# OutputIndicator_v1p1.net
KiCad netlist of a schematic drawn in EAGLE
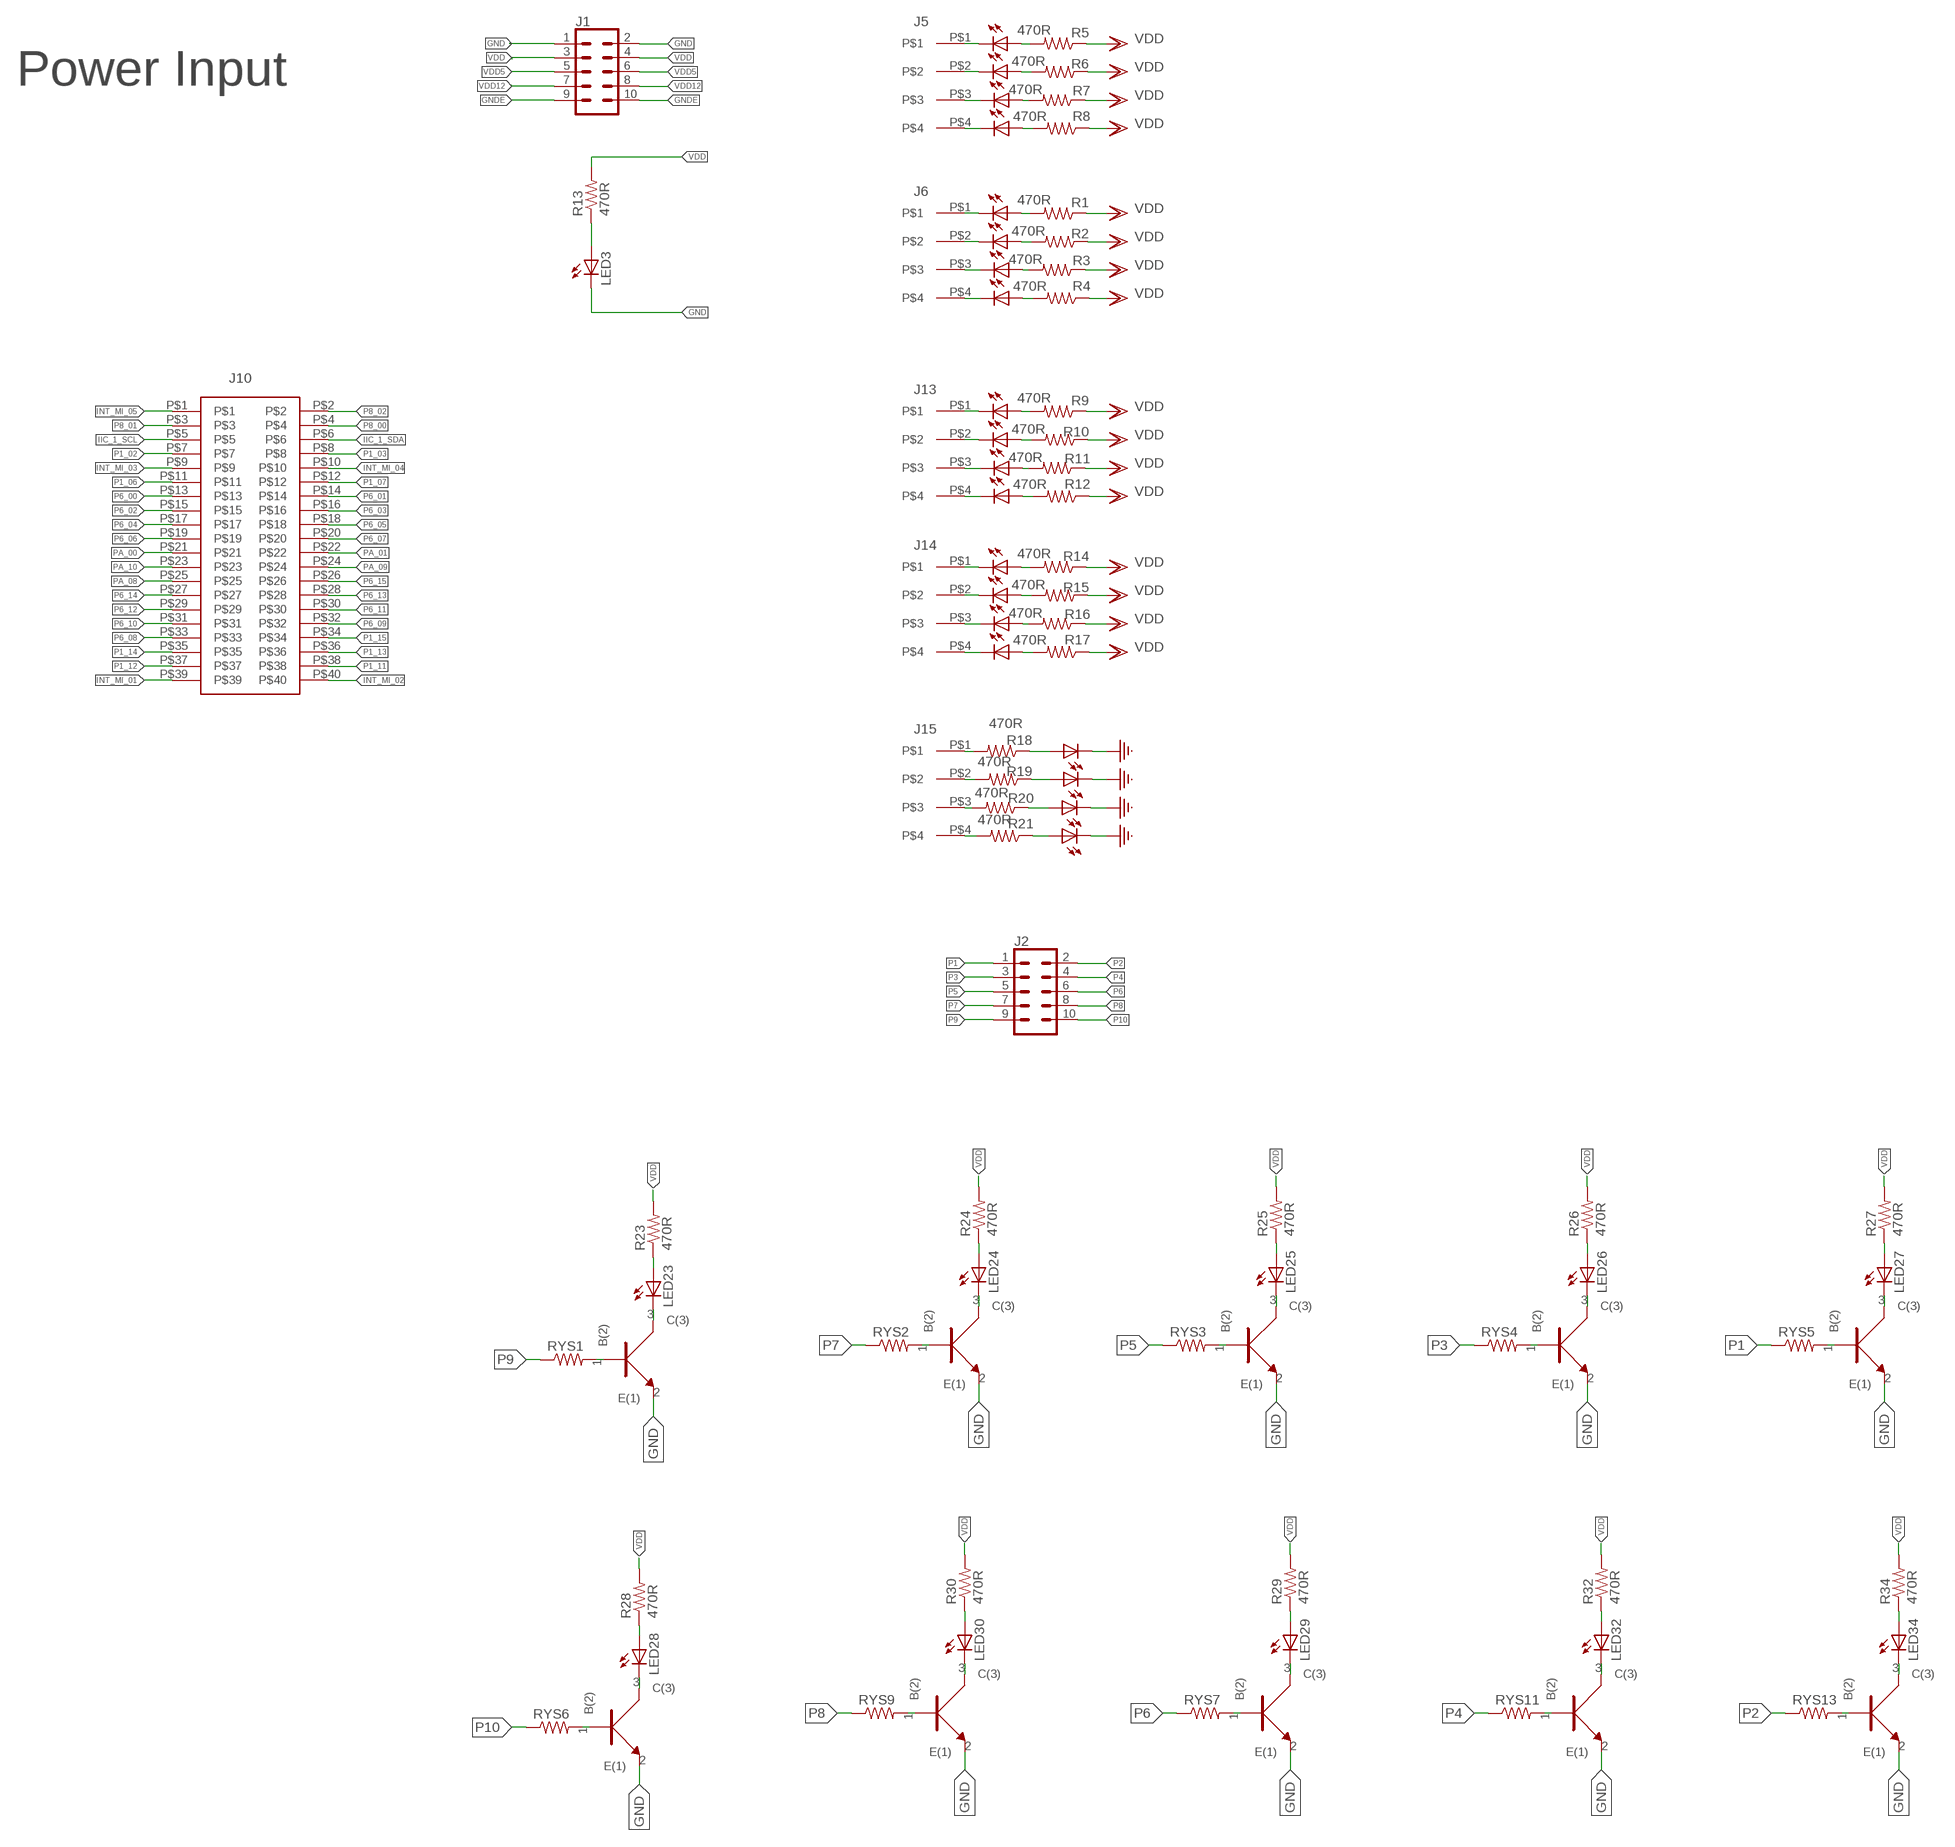
[diagram p0: schematic, sheet 1]

(export (version "E")
  (design (tool "Eeschema 10.0.6"))
  (components
    (comp (ref "J1")
      (value "CONN_05X2PTH")
      (footprint "eagle-import:2X5")
      (libsource (lib "eagle-import") (part "CONN_05X2PTH"))
    )
    (comp (ref "J2")
      (value "CONN_05X2NO_SILK")
      (footprint "eagle-import:2X5_NOSILK")
      (libsource (lib "eagle-import") (part "CONN_05X2NO_SILK"))
    )
    (comp (ref "J5")
      (value "3.81MM_1_X_4_RT_ANGLE_PLUG_HEADER")
      (footprint "eagle-import:1X4_3.81MM_PITCH")
      (libsource (lib "eagle-import") (part "3.81MM_1_X_4_RT_ANGLE_PLUG_HEADER"))
    )
    (comp (ref "J6")
      (value "3.81MM_1_X_4_RT_ANGLE_PLUG_HEADER")
      (footprint "eagle-import:1X4_3.81MM_PITCH")
      (libsource (lib "eagle-import") (part "3.81MM_1_X_4_RT_ANGLE_PLUG_HEADER"))
    )
    (comp (ref "J10")
      (value "HEADER_2_X_20_GENERIC")
      (footprint "eagle-import:HEADER_2_X_20_.1_INCH")
      (libsource (lib "eagle-import") (part "HEADER_2_X_20_GENERIC"))
    )
    (comp (ref "J13")
      (value "3.81MM_1_X_4_RT_ANGLE_PLUG_HEADER")
      (footprint "eagle-import:1X4_3.81MM_PITCH")
      (libsource (lib "eagle-import") (part "3.81MM_1_X_4_RT_ANGLE_PLUG_HEADER"))
    )
    (comp (ref "J14")
      (value "3.81MM_1_X_4_RT_ANGLE_PLUG_HEADER")
      (footprint "eagle-import:1X4_3.81MM_PITCH")
      (libsource (lib "eagle-import") (part "3.81MM_1_X_4_RT_ANGLE_PLUG_HEADER"))
    )
    (comp (ref "J15")
      (value "3.81MM_1_X_4_RT_ANGLE_PLUG_HEADER")
      (footprint "eagle-import:1X4_3.81MM_PITCH")
      (libsource (lib "eagle-import") (part "3.81MM_1_X_4_RT_ANGLE_PLUG_HEADER"))
    )
    (comp (ref "LED1")
      (value "LED_0805_GREEN")
      (footprint "eagle-import:LED_0805_GREEN")
      (libsource (lib "eagle-import") (part "LED_0805_GREEN"))
    )
    (comp (ref "LED2")
      (value "LED_0805_GREEN")
      (footprint "eagle-import:LED_0805_GREEN")
      (libsource (lib "eagle-import") (part "LED_0805_GREEN"))
    )
    (comp (ref "LED3")
      (value "LED_0805_GREEN")
      (footprint "eagle-import:LED_0805_GREEN")
      (libsource (lib "eagle-import") (part "LED_0805_GREEN"))
    )
    (comp (ref "LED4")
      (value "LED_0805_GREEN")
      (footprint "eagle-import:LED_0805_GREEN")
      (libsource (lib "eagle-import") (part "LED_0805_GREEN"))
    )
    (comp (ref "LED5")
      (value "LED_0805_GREEN")
      (footprint "eagle-import:LED_0805_GREEN")
      (libsource (lib "eagle-import") (part "LED_0805_GREEN"))
    )
    (comp (ref "LED6")
      (value "LED_0805_GREEN")
      (footprint "eagle-import:LED_0805_GREEN")
      (libsource (lib "eagle-import") (part "LED_0805_GREEN"))
    )
    (comp (ref "LED7")
      (value "LED_0805_GREEN")
      (footprint "eagle-import:LED_0805_GREEN")
      (libsource (lib "eagle-import") (part "LED_0805_GREEN"))
    )
    (comp (ref "LED8")
      (value "LED_0805_GREEN")
      (footprint "eagle-import:LED_0805_GREEN")
      (libsource (lib "eagle-import") (part "LED_0805_GREEN"))
    )
    (comp (ref "LED9")
      (value "LED_0805_GREEN")
      (footprint "eagle-import:LED_0805_GREEN")
      (libsource (lib "eagle-import") (part "LED_0805_GREEN"))
    )
    (comp (ref "LED10")
      (value "LED_0805_GREEN")
      (footprint "eagle-import:LED_0805_GREEN")
      (libsource (lib "eagle-import") (part "LED_0805_GREEN"))
    )
    (comp (ref "LED11")
      (value "LED_0805_GREEN")
      (footprint "eagle-import:LED_0805_GREEN")
      (libsource (lib "eagle-import") (part "LED_0805_GREEN"))
    )
    (comp (ref "LED12")
      (value "LED_0805_GREEN")
      (footprint "eagle-import:LED_0805_GREEN")
      (libsource (lib "eagle-import") (part "LED_0805_GREEN"))
    )
    (comp (ref "LED13")
      (value "LED_0805_GREEN")
      (footprint "eagle-import:LED_0805_GREEN")
      (libsource (lib "eagle-import") (part "LED_0805_GREEN"))
    )
    (comp (ref "LED14")
      (value "LED_0805_GREEN")
      (footprint "eagle-import:LED_0805_GREEN")
      (libsource (lib "eagle-import") (part "LED_0805_GREEN"))
    )
    (comp (ref "LED15")
      (value "LED_0805_GREEN")
      (footprint "eagle-import:LED_0805_GREEN")
      (libsource (lib "eagle-import") (part "LED_0805_GREEN"))
    )
    (comp (ref "LED16")
      (value "LED_0805_GREEN")
      (footprint "eagle-import:LED_0805_GREEN")
      (libsource (lib "eagle-import") (part "LED_0805_GREEN"))
    )
    (comp (ref "LED17")
      (value "LED_0805_GREEN")
      (footprint "eagle-import:LED_0805_GREEN")
      (libsource (lib "eagle-import") (part "LED_0805_GREEN"))
    )
    (comp (ref "LED18")
      (value "LED_0805_GREEN")
      (footprint "eagle-import:LED_0805_GREEN")
      (libsource (lib "eagle-import") (part "LED_0805_GREEN"))
    )
    (comp (ref "LED19")
      (value "LED_0805_GREEN")
      (footprint "eagle-import:LED_0805_GREEN")
      (libsource (lib "eagle-import") (part "LED_0805_GREEN"))
    )
    (comp (ref "LED20")
      (value "LED_0805_GREEN")
      (footprint "eagle-import:LED_0805_GREEN")
      (libsource (lib "eagle-import") (part "LED_0805_GREEN"))
    )
    (comp (ref "LED21")
      (value "LED_0805_GREEN")
      (footprint "eagle-import:LED_0805_GREEN")
      (libsource (lib "eagle-import") (part "LED_0805_GREEN"))
    )
    (comp (ref "LED23")
      (value "LED_0805_GREEN")
      (footprint "eagle-import:LED_0805_GREEN")
      (libsource (lib "eagle-import") (part "LED_0805_GREEN"))
    )
    (comp (ref "LED24")
      (value "LED_0805_GREEN")
      (footprint "eagle-import:LED_0805_GREEN")
      (libsource (lib "eagle-import") (part "LED_0805_GREEN"))
    )
    (comp (ref "LED25")
      (value "LED_0805_GREEN")
      (footprint "eagle-import:LED_0805_GREEN")
      (libsource (lib "eagle-import") (part "LED_0805_GREEN"))
    )
    (comp (ref "LED26")
      (value "LED_0805_GREEN")
      (footprint "eagle-import:LED_0805_GREEN")
      (libsource (lib "eagle-import") (part "LED_0805_GREEN"))
    )
    (comp (ref "LED27")
      (value "LED_0805_GREEN")
      (footprint "eagle-import:LED_0805_GREEN")
      (libsource (lib "eagle-import") (part "LED_0805_GREEN"))
    )
    (comp (ref "LED28")
      (value "LED_0805_GREEN")
      (footprint "eagle-import:LED_0805_GREEN")
      (libsource (lib "eagle-import") (part "LED_0805_GREEN"))
    )
    (comp (ref "LED29")
      (value "LED_0805_GREEN")
      (footprint "eagle-import:LED_0805_GREEN")
      (libsource (lib "eagle-import") (part "LED_0805_GREEN"))
    )
    (comp (ref "LED30")
      (value "LED_0805_GREEN")
      (footprint "eagle-import:LED_0805_GREEN")
      (libsource (lib "eagle-import") (part "LED_0805_GREEN"))
    )
    (comp (ref "LED32")
      (value "LED_0805_GREEN")
      (footprint "eagle-import:LED_0805_GREEN")
      (libsource (lib "eagle-import") (part "LED_0805_GREEN"))
    )
    (comp (ref "LED34")
      (value "LED_0805_GREEN")
      (footprint "eagle-import:LED_0805_GREEN")
      (libsource (lib "eagle-import") (part "LED_0805_GREEN"))
    )
    (comp (ref "R1")
      (value "470R")
      (footprint "eagle-import:0402")
      (libsource (lib "eagle-import") (part "R_0402"))
    )
    (comp (ref "R2")
      (value "470R")
      (footprint "eagle-import:0402")
      (libsource (lib "eagle-import") (part "R_0402"))
    )
    (comp (ref "R3")
      (value "470R")
      (footprint "eagle-import:0402")
      (libsource (lib "eagle-import") (part "R_0402"))
    )
    (comp (ref "R4")
      (value "470R")
      (footprint "eagle-import:0402")
      (libsource (lib "eagle-import") (part "R_0402"))
    )
    (comp (ref "R5")
      (value "470R")
      (footprint "eagle-import:0402")
      (libsource (lib "eagle-import") (part "R_0402"))
    )
    (comp (ref "R6")
      (value "470R")
      (footprint "eagle-import:0402")
      (libsource (lib "eagle-import") (part "R_0402"))
    )
    (comp (ref "R7")
      (value "470R")
      (footprint "eagle-import:0402")
      (libsource (lib "eagle-import") (part "R_0402"))
    )
    (comp (ref "R8")
      (value "470R")
      (footprint "eagle-import:0402")
      (libsource (lib "eagle-import") (part "R_0402"))
    )
    (comp (ref "R9")
      (value "470R")
      (footprint "eagle-import:0402")
      (libsource (lib "eagle-import") (part "R_0402"))
    )
    (comp (ref "R10")
      (value "470R")
      (footprint "eagle-import:0402")
      (libsource (lib "eagle-import") (part "R_0402"))
    )
    (comp (ref "R11")
      (value "470R")
      (footprint "eagle-import:0402")
      (libsource (lib "eagle-import") (part "R_0402"))
    )
    (comp (ref "R12")
      (value "470R")
      (footprint "eagle-import:0402")
      (libsource (lib "eagle-import") (part "R_0402"))
    )
    (comp (ref "R13")
      (value "470R")
      (footprint "eagle-import:0402")
      (libsource (lib "eagle-import") (part "R_0402"))
    )
    (comp (ref "R14")
      (value "470R")
      (footprint "eagle-import:0402")
      (libsource (lib "eagle-import") (part "R_0402"))
    )
    (comp (ref "R15")
      (value "470R")
      (footprint "eagle-import:0402")
      (libsource (lib "eagle-import") (part "R_0402"))
    )
    (comp (ref "R16")
      (value "470R")
      (footprint "eagle-import:0402")
      (libsource (lib "eagle-import") (part "R_0402"))
    )
    (comp (ref "R17")
      (value "470R")
      (footprint "eagle-import:0402")
      (libsource (lib "eagle-import") (part "R_0402"))
    )
    (comp (ref "R18")
      (value "470R")
      (footprint "eagle-import:0402")
      (libsource (lib "eagle-import") (part "R_0402"))
    )
    (comp (ref "R19")
      (value "470R")
      (footprint "eagle-import:0402")
      (libsource (lib "eagle-import") (part "R_0402"))
    )
    (comp (ref "R20")
      (value "470R")
      (footprint "eagle-import:0402")
      (libsource (lib "eagle-import") (part "R_0402"))
    )
    (comp (ref "R21")
      (value "470R")
      (footprint "eagle-import:0402")
      (libsource (lib "eagle-import") (part "R_0402"))
    )
    (comp (ref "R23")
      (value "470R")
      (footprint "eagle-import:0402")
      (libsource (lib "eagle-import") (part "R_0402"))
    )
    (comp (ref "R24")
      (value "470R")
      (footprint "eagle-import:0402")
      (libsource (lib "eagle-import") (part "R_0402"))
    )
    (comp (ref "R25")
      (value "470R")
      (footprint "eagle-import:0402")
      (libsource (lib "eagle-import") (part "R_0402"))
    )
    (comp (ref "R26")
      (value "470R")
      (footprint "eagle-import:0402")
      (libsource (lib "eagle-import") (part "R_0402"))
    )
    (comp (ref "R27")
      (value "470R")
      (footprint "eagle-import:0402")
      (libsource (lib "eagle-import") (part "R_0402"))
    )
    (comp (ref "R28")
      (value "470R")
      (footprint "eagle-import:0402")
      (libsource (lib "eagle-import") (part "R_0402"))
    )
    (comp (ref "R29")
      (value "470R")
      (footprint "eagle-import:0402")
      (libsource (lib "eagle-import") (part "R_0402"))
    )
    (comp (ref "R30")
      (value "470R")
      (footprint "eagle-import:0402")
      (libsource (lib "eagle-import") (part "R_0402"))
    )
    (comp (ref "R32")
      (value "470R")
      (footprint "eagle-import:0402")
      (libsource (lib "eagle-import") (part "R_0402"))
    )
    (comp (ref "R34")
      (value "470R")
      (footprint "eagle-import:0402")
      (libsource (lib "eagle-import") (part "R_0402"))
    )
    (comp (ref "RYS1")
      (value "1K")
      (footprint "eagle-import:0402")
      (libsource (lib "eagle-import") (part "R_0402"))
    )
    (comp (ref "RYS2")
      (value "1K")
      (footprint "eagle-import:0402")
      (libsource (lib "eagle-import") (part "R_0402"))
    )
    (comp (ref "RYS3")
      (value "1K")
      (footprint "eagle-import:0402")
      (libsource (lib "eagle-import") (part "R_0402"))
    )
    (comp (ref "RYS4")
      (value "1K")
      (footprint "eagle-import:0402")
      (libsource (lib "eagle-import") (part "R_0402"))
    )
    (comp (ref "RYS5")
      (value "1K")
      (footprint "eagle-import:0402")
      (libsource (lib "eagle-import") (part "R_0402"))
    )
    (comp (ref "RYS6")
      (value "1K")
      (footprint "eagle-import:0402")
      (libsource (lib "eagle-import") (part "R_0402"))
    )
    (comp (ref "RYS7")
      (value "1K")
      (footprint "eagle-import:0402")
      (libsource (lib "eagle-import") (part "R_0402"))
    )
    (comp (ref "RYS9")
      (value "1K")
      (footprint "eagle-import:0402")
      (libsource (lib "eagle-import") (part "R_0402"))
    )
    (comp (ref "RYS11")
      (value "1K")
      (footprint "eagle-import:0402")
      (libsource (lib "eagle-import") (part "R_0402"))
    )
    (comp (ref "RYS13")
      (value "1K")
      (footprint "eagle-import:0402")
      (libsource (lib "eagle-import") (part "R_0402"))
    )
    (comp (ref "U1")
      (value "BC846BW")
      (footprint "eagle-import:SOT323")
      (libsource (lib "eagle-import") (part "BC846BW"))
    )
    (comp (ref "U2")
      (value "BC846BW")
      (footprint "eagle-import:SOT323")
      (libsource (lib "eagle-import") (part "BC846BW"))
    )
    (comp (ref "U3")
      (value "BC846BW")
      (footprint "eagle-import:SOT323")
      (libsource (lib "eagle-import") (part "BC846BW"))
    )
    (comp (ref "U4")
      (value "BC846BW")
      (footprint "eagle-import:SOT323")
      (libsource (lib "eagle-import") (part "BC846BW"))
    )
    (comp (ref "U5")
      (value "BC846BW")
      (footprint "eagle-import:SOT323")
      (libsource (lib "eagle-import") (part "BC846BW"))
    )
    (comp (ref "U6")
      (value "BC846BW")
      (footprint "eagle-import:SOT323")
      (libsource (lib "eagle-import") (part "BC846BW"))
    )
    (comp (ref "U7")
      (value "BC846BW")
      (footprint "eagle-import:SOT323")
      (libsource (lib "eagle-import") (part "BC846BW"))
    )
    (comp (ref "U8")
      (value "BC846BW")
      (footprint "eagle-import:SOT323")
      (libsource (lib "eagle-import") (part "BC846BW"))
    )
    (comp (ref "U10")
      (value "BC846BW")
      (footprint "eagle-import:SOT323")
      (libsource (lib "eagle-import") (part "BC846BW"))
    )
    (comp (ref "U12")
      (value "BC846BW")
      (footprint "eagle-import:SOT323")
      (libsource (lib "eagle-import") (part "BC846BW"))
    )
  )
  (nets
    (net (code "1") (name "GND") (class "Default")
      (node (ref "J1") (pin "1") (pinfunction "1_1") (pintype "passive"))
      (node (ref "J1") (pin "2") (pinfunction "2_2") (pintype "passive"))
      (node (ref "LED18") (pin "C") (pinfunction "C_C") (pintype "passive"))
      (node (ref "LED19") (pin "C") (pinfunction "C_C") (pintype "passive"))
      (node (ref "LED20") (pin "C") (pinfunction "C_C") (pintype "passive"))
      (node (ref "LED21") (pin "C") (pinfunction "C_C") (pintype "passive"))
      (node (ref "LED3") (pin "C") (pinfunction "C_C") (pintype "passive"))
      (node (ref "U1") (pin "2") (pinfunction "E(1)_2") (pintype "output"))
      (node (ref "U10") (pin "2") (pinfunction "E(1)_2") (pintype "output"))
      (node (ref "U12") (pin "2") (pinfunction "E(1)_2") (pintype "output"))
      (node (ref "U2") (pin "2") (pinfunction "E(1)_2") (pintype "output"))
      (node (ref "U3") (pin "2") (pinfunction "E(1)_2") (pintype "output"))
      (node (ref "U4") (pin "2") (pinfunction "E(1)_2") (pintype "output"))
      (node (ref "U5") (pin "2") (pinfunction "E(1)_2") (pintype "output"))
      (node (ref "U6") (pin "2") (pinfunction "E(1)_2") (pintype "output"))
      (node (ref "U7") (pin "2") (pinfunction "E(1)_2") (pintype "output"))
      (node (ref "U8") (pin "2") (pinfunction "E(1)_2") (pintype "output"))
    )
    (net (code "2") (name "GNDE") (class "Default")
      (node (ref "J1") (pin "10") (pinfunction "10_10") (pintype "passive"))
      (node (ref "J1") (pin "9") (pinfunction "9_9") (pintype "passive"))
    )
    (net (code "3") (name "IIC_1_SCL") (class "Default")
      (node (ref "J10") (pin "P$5") (pinfunction "P$5_P$5") (pintype "bidirectional"))
    )
    (net (code "4") (name "IIC_1_SDA") (class "Default")
      (node (ref "J10") (pin "P$6") (pinfunction "P$6_P$6") (pintype "bidirectional"))
    )
    (net (code "5") (name "INT_MI_01") (class "Default")
      (node (ref "J10") (pin "P$39") (pinfunction "P$39_P$39") (pintype "bidirectional"))
    )
    (net (code "6") (name "INT_MI_02") (class "Default")
      (node (ref "J10") (pin "P$40") (pinfunction "P$40_P$40") (pintype "bidirectional"))
    )
    (net (code "7") (name "INT_MI_03") (class "Default")
      (node (ref "J10") (pin "P$9") (pinfunction "P$9_P$9") (pintype "bidirectional"))
    )
    (net (code "8") (name "INT_MI_04") (class "Default")
      (node (ref "J10") (pin "P$10") (pinfunction "P$10_P$10") (pintype "bidirectional"))
    )
    (net (code "9") (name "INT_MI_05") (class "Default")
      (node (ref "J10") (pin "P$1") (pinfunction "P$1_P$1") (pintype "bidirectional"))
    )
    (net (code "10") (name "Net-(J5-PadP$1)") (class "Default")
      (node (ref "J5") (pin "P$1") (pinfunction "P$1_P$1") (pintype "bidirectional"))
      (node (ref "LED6") (pin "C") (pinfunction "C_C") (pintype "passive"))
    )
    (net (code "11") (name "Net-(J5-PadP$2)") (class "Default")
      (node (ref "J5") (pin "P$2") (pinfunction "P$2_P$2") (pintype "bidirectional"))
      (node (ref "LED7") (pin "C") (pinfunction "C_C") (pintype "passive"))
    )
    (net (code "12") (name "Net-(J5-PadP$3)") (class "Default")
      (node (ref "J5") (pin "P$3") (pinfunction "P$3_P$3") (pintype "bidirectional"))
      (node (ref "LED8") (pin "C") (pinfunction "C_C") (pintype "passive"))
    )
    (net (code "13") (name "Net-(J5-PadP$4)") (class "Default")
      (node (ref "J5") (pin "P$4") (pinfunction "P$4_P$4") (pintype "bidirectional"))
      (node (ref "LED9") (pin "C") (pinfunction "C_C") (pintype "passive"))
    )
    (net (code "14") (name "Net-(J6-PadP$1)") (class "Default")
      (node (ref "J6") (pin "P$1") (pinfunction "P$1_P$1") (pintype "bidirectional"))
      (node (ref "LED1") (pin "C") (pinfunction "C_C") (pintype "passive"))
    )
    (net (code "15") (name "Net-(J6-PadP$2)") (class "Default")
      (node (ref "J6") (pin "P$2") (pinfunction "P$2_P$2") (pintype "bidirectional"))
      (node (ref "LED2") (pin "C") (pinfunction "C_C") (pintype "passive"))
    )
    (net (code "16") (name "Net-(J6-PadP$3)") (class "Default")
      (node (ref "J6") (pin "P$3") (pinfunction "P$3_P$3") (pintype "bidirectional"))
      (node (ref "LED4") (pin "C") (pinfunction "C_C") (pintype "passive"))
    )
    (net (code "17") (name "Net-(J6-PadP$4)") (class "Default")
      (node (ref "J6") (pin "P$4") (pinfunction "P$4_P$4") (pintype "bidirectional"))
      (node (ref "LED5") (pin "C") (pinfunction "C_C") (pintype "passive"))
    )
    (net (code "18") (name "Net-(J13-PadP$1)") (class "Default")
      (node (ref "J13") (pin "P$1") (pinfunction "P$1_P$1") (pintype "bidirectional"))
      (node (ref "LED10") (pin "C") (pinfunction "C_C") (pintype "passive"))
    )
    (net (code "19") (name "Net-(J13-PadP$2)") (class "Default")
      (node (ref "J13") (pin "P$2") (pinfunction "P$2_P$2") (pintype "bidirectional"))
      (node (ref "LED11") (pin "C") (pinfunction "C_C") (pintype "passive"))
    )
    (net (code "20") (name "Net-(J13-PadP$3)") (class "Default")
      (node (ref "J13") (pin "P$3") (pinfunction "P$3_P$3") (pintype "bidirectional"))
      (node (ref "LED12") (pin "C") (pinfunction "C_C") (pintype "passive"))
    )
    (net (code "21") (name "Net-(J13-PadP$4)") (class "Default")
      (node (ref "J13") (pin "P$4") (pinfunction "P$4_P$4") (pintype "bidirectional"))
      (node (ref "LED13") (pin "C") (pinfunction "C_C") (pintype "passive"))
    )
    (net (code "22") (name "Net-(J14-PadP$1)") (class "Default")
      (node (ref "J14") (pin "P$1") (pinfunction "P$1_P$1") (pintype "bidirectional"))
      (node (ref "LED14") (pin "C") (pinfunction "C_C") (pintype "passive"))
    )
    (net (code "23") (name "Net-(J14-PadP$2)") (class "Default")
      (node (ref "J14") (pin "P$2") (pinfunction "P$2_P$2") (pintype "bidirectional"))
      (node (ref "LED15") (pin "C") (pinfunction "C_C") (pintype "passive"))
    )
    (net (code "24") (name "Net-(J14-PadP$3)") (class "Default")
      (node (ref "J14") (pin "P$3") (pinfunction "P$3_P$3") (pintype "bidirectional"))
      (node (ref "LED16") (pin "C") (pinfunction "C_C") (pintype "passive"))
    )
    (net (code "25") (name "Net-(J14-PadP$4)") (class "Default")
      (node (ref "J14") (pin "P$4") (pinfunction "P$4_P$4") (pintype "bidirectional"))
      (node (ref "LED17") (pin "C") (pinfunction "C_C") (pintype "passive"))
    )
    (net (code "26") (name "Net-(R1-2)") (class "Default")
      (node (ref "LED1") (pin "A") (pinfunction "A_A") (pintype "passive"))
      (node (ref "R1") (pin "P$2") (pinfunction "2_P$2") (pintype "passive"))
    )
    (net (code "27") (name "Net-(R2-2)") (class "Default")
      (node (ref "LED2") (pin "A") (pinfunction "A_A") (pintype "passive"))
      (node (ref "R2") (pin "P$2") (pinfunction "2_P$2") (pintype "passive"))
    )
    (net (code "28") (name "Net-(R3-2)") (class "Default")
      (node (ref "LED4") (pin "A") (pinfunction "A_A") (pintype "passive"))
      (node (ref "R3") (pin "P$2") (pinfunction "2_P$2") (pintype "passive"))
    )
    (net (code "29") (name "Net-(R4-2)") (class "Default")
      (node (ref "LED5") (pin "A") (pinfunction "A_A") (pintype "passive"))
      (node (ref "R4") (pin "P$2") (pinfunction "2_P$2") (pintype "passive"))
    )
    (net (code "30") (name "Net-(R5-2)") (class "Default")
      (node (ref "LED6") (pin "A") (pinfunction "A_A") (pintype "passive"))
      (node (ref "R5") (pin "P$2") (pinfunction "2_P$2") (pintype "passive"))
    )
    (net (code "31") (name "Net-(R6-2)") (class "Default")
      (node (ref "LED7") (pin "A") (pinfunction "A_A") (pintype "passive"))
      (node (ref "R6") (pin "P$2") (pinfunction "2_P$2") (pintype "passive"))
    )
    (net (code "32") (name "Net-(R7-2)") (class "Default")
      (node (ref "LED8") (pin "A") (pinfunction "A_A") (pintype "passive"))
      (node (ref "R7") (pin "P$2") (pinfunction "2_P$2") (pintype "passive"))
    )
    (net (code "33") (name "Net-(R8-2)") (class "Default")
      (node (ref "LED9") (pin "A") (pinfunction "A_A") (pintype "passive"))
      (node (ref "R8") (pin "P$2") (pinfunction "2_P$2") (pintype "passive"))
    )
    (net (code "34") (name "Net-(R9-2)") (class "Default")
      (node (ref "LED10") (pin "A") (pinfunction "A_A") (pintype "passive"))
      (node (ref "R9") (pin "P$2") (pinfunction "2_P$2") (pintype "passive"))
    )
    (net (code "35") (name "Net-(R10-2)") (class "Default")
      (node (ref "LED11") (pin "A") (pinfunction "A_A") (pintype "passive"))
      (node (ref "R10") (pin "P$2") (pinfunction "2_P$2") (pintype "passive"))
    )
    (net (code "36") (name "Net-(R11-2)") (class "Default")
      (node (ref "LED12") (pin "A") (pinfunction "A_A") (pintype "passive"))
      (node (ref "R11") (pin "P$2") (pinfunction "2_P$2") (pintype "passive"))
    )
    (net (code "37") (name "Net-(R12-2)") (class "Default")
      (node (ref "LED13") (pin "A") (pinfunction "A_A") (pintype "passive"))
      (node (ref "R12") (pin "P$2") (pinfunction "2_P$2") (pintype "passive"))
    )
    (net (code "38") (name "Net-(R13-1)") (class "Default")
      (node (ref "LED3") (pin "A") (pinfunction "A_A") (pintype "passive"))
      (node (ref "R13") (pin "P$1") (pinfunction "1_P$1") (pintype "passive"))
    )
    (net (code "39") (name "Net-(R14-2)") (class "Default")
      (node (ref "LED14") (pin "A") (pinfunction "A_A") (pintype "passive"))
      (node (ref "R14") (pin "P$2") (pinfunction "2_P$2") (pintype "passive"))
    )
    (net (code "40") (name "Net-(R15-2)") (class "Default")
      (node (ref "LED15") (pin "A") (pinfunction "A_A") (pintype "passive"))
      (node (ref "R15") (pin "P$2") (pinfunction "2_P$2") (pintype "passive"))
    )
    (net (code "41") (name "Net-(R16-2)") (class "Default")
      (node (ref "LED16") (pin "A") (pinfunction "A_A") (pintype "passive"))
      (node (ref "R16") (pin "P$2") (pinfunction "2_P$2") (pintype "passive"))
    )
    (net (code "42") (name "Net-(R17-2)") (class "Default")
      (node (ref "LED17") (pin "A") (pinfunction "A_A") (pintype "passive"))
      (node (ref "R17") (pin "P$2") (pinfunction "2_P$2") (pintype "passive"))
    )
    (net (code "43") (name "Net-(R18-1)") (class "Default")
      (node (ref "LED18") (pin "A") (pinfunction "A_A") (pintype "passive"))
      (node (ref "R18") (pin "P$1") (pinfunction "1_P$1") (pintype "passive"))
    )
    (net (code "44") (name "Net-(R18-2)") (class "Default")
      (node (ref "J15") (pin "P$1") (pinfunction "P$1_P$1") (pintype "bidirectional"))
      (node (ref "R18") (pin "P$2") (pinfunction "2_P$2") (pintype "passive"))
    )
    (net (code "45") (name "Net-(R19-1)") (class "Default")
      (node (ref "LED19") (pin "A") (pinfunction "A_A") (pintype "passive"))
      (node (ref "R19") (pin "P$1") (pinfunction "1_P$1") (pintype "passive"))
    )
    (net (code "46") (name "Net-(R19-2)") (class "Default")
      (node (ref "J15") (pin "P$2") (pinfunction "P$2_P$2") (pintype "bidirectional"))
      (node (ref "R19") (pin "P$2") (pinfunction "2_P$2") (pintype "passive"))
    )
    (net (code "47") (name "Net-(R20-1)") (class "Default")
      (node (ref "LED20") (pin "A") (pinfunction "A_A") (pintype "passive"))
      (node (ref "R20") (pin "P$1") (pinfunction "1_P$1") (pintype "passive"))
    )
    (net (code "48") (name "Net-(R20-2)") (class "Default")
      (node (ref "J15") (pin "P$3") (pinfunction "P$3_P$3") (pintype "bidirectional"))
      (node (ref "R20") (pin "P$2") (pinfunction "2_P$2") (pintype "passive"))
    )
    (net (code "49") (name "Net-(R21-1)") (class "Default")
      (node (ref "LED21") (pin "A") (pinfunction "A_A") (pintype "passive"))
      (node (ref "R21") (pin "P$1") (pinfunction "1_P$1") (pintype "passive"))
    )
    (net (code "50") (name "Net-(R21-2)") (class "Default")
      (node (ref "J15") (pin "P$4") (pinfunction "P$4_P$4") (pintype "bidirectional"))
      (node (ref "R21") (pin "P$2") (pinfunction "2_P$2") (pintype "passive"))
    )
    (net (code "51") (name "Net-(R23-1)") (class "Default")
      (node (ref "LED23") (pin "A") (pinfunction "A_A") (pintype "passive"))
      (node (ref "R23") (pin "P$1") (pinfunction "1_P$1") (pintype "passive"))
    )
    (net (code "52") (name "Net-(R24-1)") (class "Default")
      (node (ref "LED24") (pin "A") (pinfunction "A_A") (pintype "passive"))
      (node (ref "R24") (pin "P$1") (pinfunction "1_P$1") (pintype "passive"))
    )
    (net (code "53") (name "Net-(R25-1)") (class "Default")
      (node (ref "LED25") (pin "A") (pinfunction "A_A") (pintype "passive"))
      (node (ref "R25") (pin "P$1") (pinfunction "1_P$1") (pintype "passive"))
    )
    (net (code "54") (name "Net-(R26-1)") (class "Default")
      (node (ref "LED26") (pin "A") (pinfunction "A_A") (pintype "passive"))
      (node (ref "R26") (pin "P$1") (pinfunction "1_P$1") (pintype "passive"))
    )
    (net (code "55") (name "Net-(R27-1)") (class "Default")
      (node (ref "LED27") (pin "A") (pinfunction "A_A") (pintype "passive"))
      (node (ref "R27") (pin "P$1") (pinfunction "1_P$1") (pintype "passive"))
    )
    (net (code "56") (name "Net-(R28-1)") (class "Default")
      (node (ref "LED28") (pin "A") (pinfunction "A_A") (pintype "passive"))
      (node (ref "R28") (pin "P$1") (pinfunction "1_P$1") (pintype "passive"))
    )
    (net (code "57") (name "Net-(R29-1)") (class "Default")
      (node (ref "LED29") (pin "A") (pinfunction "A_A") (pintype "passive"))
      (node (ref "R29") (pin "P$1") (pinfunction "1_P$1") (pintype "passive"))
    )
    (net (code "58") (name "Net-(R30-1)") (class "Default")
      (node (ref "LED30") (pin "A") (pinfunction "A_A") (pintype "passive"))
      (node (ref "R30") (pin "P$1") (pinfunction "1_P$1") (pintype "passive"))
    )
    (net (code "59") (name "Net-(R32-1)") (class "Default")
      (node (ref "LED32") (pin "A") (pinfunction "A_A") (pintype "passive"))
      (node (ref "R32") (pin "P$1") (pinfunction "1_P$1") (pintype "passive"))
    )
    (net (code "60") (name "Net-(R34-1)") (class "Default")
      (node (ref "LED34") (pin "A") (pinfunction "A_A") (pintype "passive"))
      (node (ref "R34") (pin "P$1") (pinfunction "1_P$1") (pintype "passive"))
    )
    (net (code "61") (name "Net-(RYS1-2)") (class "Default")
      (node (ref "RYS1") (pin "P$2") (pinfunction "2_P$2") (pintype "passive"))
      (node (ref "U1") (pin "1") (pinfunction "B(2)_1") (pintype "input"))
    )
    (net (code "62") (name "Net-(RYS2-2)") (class "Default")
      (node (ref "RYS2") (pin "P$2") (pinfunction "2_P$2") (pintype "passive"))
      (node (ref "U2") (pin "1") (pinfunction "B(2)_1") (pintype "input"))
    )
    (net (code "63") (name "Net-(RYS3-2)") (class "Default")
      (node (ref "RYS3") (pin "P$2") (pinfunction "2_P$2") (pintype "passive"))
      (node (ref "U3") (pin "1") (pinfunction "B(2)_1") (pintype "input"))
    )
    (net (code "64") (name "Net-(RYS4-2)") (class "Default")
      (node (ref "RYS4") (pin "P$2") (pinfunction "2_P$2") (pintype "passive"))
      (node (ref "U4") (pin "1") (pinfunction "B(2)_1") (pintype "input"))
    )
    (net (code "65") (name "Net-(RYS5-2)") (class "Default")
      (node (ref "RYS5") (pin "P$2") (pinfunction "2_P$2") (pintype "passive"))
      (node (ref "U5") (pin "1") (pinfunction "B(2)_1") (pintype "input"))
    )
    (net (code "66") (name "Net-(RYS6-2)") (class "Default")
      (node (ref "RYS6") (pin "P$2") (pinfunction "2_P$2") (pintype "passive"))
      (node (ref "U6") (pin "1") (pinfunction "B(2)_1") (pintype "input"))
    )
    (net (code "67") (name "Net-(RYS7-2)") (class "Default")
      (node (ref "RYS7") (pin "P$2") (pinfunction "2_P$2") (pintype "passive"))
      (node (ref "U7") (pin "1") (pinfunction "B(2)_1") (pintype "input"))
    )
    (net (code "68") (name "Net-(RYS9-2)") (class "Default")
      (node (ref "RYS9") (pin "P$2") (pinfunction "2_P$2") (pintype "passive"))
      (node (ref "U8") (pin "1") (pinfunction "B(2)_1") (pintype "input"))
    )
    (net (code "69") (name "Net-(RYS11-2)") (class "Default")
      (node (ref "RYS11") (pin "P$2") (pinfunction "2_P$2") (pintype "passive"))
      (node (ref "U10") (pin "1") (pinfunction "B(2)_1") (pintype "input"))
    )
    (net (code "70") (name "Net-(RYS13-2)") (class "Default")
      (node (ref "RYS13") (pin "P$2") (pinfunction "2_P$2") (pintype "passive"))
      (node (ref "U12") (pin "1") (pinfunction "B(2)_1") (pintype "input"))
    )
    (net (code "71") (name "Net-(U1-C(3))") (class "Default")
      (node (ref "LED23") (pin "C") (pinfunction "C_C") (pintype "passive"))
      (node (ref "U1") (pin "3") (pinfunction "C(3)_3") (pintype "input"))
    )
    (net (code "72") (name "Net-(U2-C(3))") (class "Default")
      (node (ref "LED24") (pin "C") (pinfunction "C_C") (pintype "passive"))
      (node (ref "U2") (pin "3") (pinfunction "C(3)_3") (pintype "input"))
    )
    (net (code "73") (name "Net-(U3-C(3))") (class "Default")
      (node (ref "LED25") (pin "C") (pinfunction "C_C") (pintype "passive"))
      (node (ref "U3") (pin "3") (pinfunction "C(3)_3") (pintype "input"))
    )
    (net (code "74") (name "Net-(U4-C(3))") (class "Default")
      (node (ref "LED26") (pin "C") (pinfunction "C_C") (pintype "passive"))
      (node (ref "U4") (pin "3") (pinfunction "C(3)_3") (pintype "input"))
    )
    (net (code "75") (name "Net-(U5-C(3))") (class "Default")
      (node (ref "LED27") (pin "C") (pinfunction "C_C") (pintype "passive"))
      (node (ref "U5") (pin "3") (pinfunction "C(3)_3") (pintype "input"))
    )
    (net (code "76") (name "Net-(U6-C(3))") (class "Default")
      (node (ref "LED28") (pin "C") (pinfunction "C_C") (pintype "passive"))
      (node (ref "U6") (pin "3") (pinfunction "C(3)_3") (pintype "input"))
    )
    (net (code "77") (name "Net-(U7-C(3))") (class "Default")
      (node (ref "LED29") (pin "C") (pinfunction "C_C") (pintype "passive"))
      (node (ref "U7") (pin "3") (pinfunction "C(3)_3") (pintype "input"))
    )
    (net (code "78") (name "Net-(U8-C(3))") (class "Default")
      (node (ref "LED30") (pin "C") (pinfunction "C_C") (pintype "passive"))
      (node (ref "U8") (pin "3") (pinfunction "C(3)_3") (pintype "input"))
    )
    (net (code "79") (name "Net-(U10-C(3))") (class "Default")
      (node (ref "LED32") (pin "C") (pinfunction "C_C") (pintype "passive"))
      (node (ref "U10") (pin "3") (pinfunction "C(3)_3") (pintype "input"))
    )
    (net (code "80") (name "Net-(U12-C(3))") (class "Default")
      (node (ref "LED34") (pin "C") (pinfunction "C_C") (pintype "passive"))
      (node (ref "U12") (pin "3") (pinfunction "C(3)_3") (pintype "input"))
    )
    (net (code "81") (name "P1") (class "Default")
      (node (ref "J2") (pin "1") (pinfunction "1_1") (pintype "passive"))
      (node (ref "RYS5") (pin "P$1") (pinfunction "1_P$1") (pintype "passive"))
    )
    (net (code "82") (name "P1_02") (class "Default")
      (node (ref "J10") (pin "P$7") (pinfunction "P$7_P$7") (pintype "bidirectional"))
    )
    (net (code "83") (name "P1_03") (class "Default")
      (node (ref "J10") (pin "P$8") (pinfunction "P$8_P$8") (pintype "bidirectional"))
    )
    (net (code "84") (name "P1_06") (class "Default")
      (node (ref "J10") (pin "P$11") (pinfunction "P$11_P$11") (pintype "bidirectional"))
    )
    (net (code "85") (name "P1_07") (class "Default")
      (node (ref "J10") (pin "P$12") (pinfunction "P$12_P$12") (pintype "bidirectional"))
    )
    (net (code "86") (name "P1_11") (class "Default")
      (node (ref "J10") (pin "P$38") (pinfunction "P$38_P$38") (pintype "bidirectional"))
    )
    (net (code "87") (name "P1_12") (class "Default")
      (node (ref "J10") (pin "P$37") (pinfunction "P$37_P$37") (pintype "bidirectional"))
    )
    (net (code "88") (name "P1_13") (class "Default")
      (node (ref "J10") (pin "P$36") (pinfunction "P$36_P$36") (pintype "bidirectional"))
    )
    (net (code "89") (name "P1_14") (class "Default")
      (node (ref "J10") (pin "P$35") (pinfunction "P$35_P$35") (pintype "bidirectional"))
    )
    (net (code "90") (name "P1_15") (class "Default")
      (node (ref "J10") (pin "P$34") (pinfunction "P$34_P$34") (pintype "bidirectional"))
    )
    (net (code "91") (name "P2") (class "Default")
      (node (ref "J2") (pin "2") (pinfunction "2_2") (pintype "passive"))
      (node (ref "RYS13") (pin "P$1") (pinfunction "1_P$1") (pintype "passive"))
    )
    (net (code "92") (name "P3") (class "Default")
      (node (ref "J2") (pin "3") (pinfunction "3_3") (pintype "passive"))
      (node (ref "RYS4") (pin "P$1") (pinfunction "1_P$1") (pintype "passive"))
    )
    (net (code "93") (name "P4") (class "Default")
      (node (ref "J2") (pin "4") (pinfunction "4_4") (pintype "passive"))
      (node (ref "RYS11") (pin "P$1") (pinfunction "1_P$1") (pintype "passive"))
    )
    (net (code "94") (name "P5") (class "Default")
      (node (ref "J2") (pin "5") (pinfunction "5_5") (pintype "passive"))
      (node (ref "RYS3") (pin "P$1") (pinfunction "1_P$1") (pintype "passive"))
    )
    (net (code "95") (name "P6") (class "Default")
      (node (ref "J2") (pin "6") (pinfunction "6_6") (pintype "passive"))
      (node (ref "RYS7") (pin "P$1") (pinfunction "1_P$1") (pintype "passive"))
    )
    (net (code "96") (name "P6_00") (class "Default")
      (node (ref "J10") (pin "P$13") (pinfunction "P$13_P$13") (pintype "bidirectional"))
    )
    (net (code "97") (name "P6_01") (class "Default")
      (node (ref "J10") (pin "P$14") (pinfunction "P$14_P$14") (pintype "bidirectional"))
    )
    (net (code "98") (name "P6_02") (class "Default")
      (node (ref "J10") (pin "P$15") (pinfunction "P$15_P$15") (pintype "bidirectional"))
    )
    (net (code "99") (name "P6_03") (class "Default")
      (node (ref "J10") (pin "P$16") (pinfunction "P$16_P$16") (pintype "bidirectional"))
    )
    (net (code "100") (name "P6_04") (class "Default")
      (node (ref "J10") (pin "P$17") (pinfunction "P$17_P$17") (pintype "bidirectional"))
    )
    (net (code "101") (name "P6_05") (class "Default")
      (node (ref "J10") (pin "P$18") (pinfunction "P$18_P$18") (pintype "bidirectional"))
    )
    (net (code "102") (name "P6_06") (class "Default")
      (node (ref "J10") (pin "P$19") (pinfunction "P$19_P$19") (pintype "bidirectional"))
    )
    (net (code "103") (name "P6_07") (class "Default")
      (node (ref "J10") (pin "P$20") (pinfunction "P$20_P$20") (pintype "bidirectional"))
    )
    (net (code "104") (name "P6_08") (class "Default")
      (node (ref "J10") (pin "P$33") (pinfunction "P$33_P$33") (pintype "bidirectional"))
    )
    (net (code "105") (name "P6_09") (class "Default")
      (node (ref "J10") (pin "P$32") (pinfunction "P$32_P$32") (pintype "bidirectional"))
    )
    (net (code "106") (name "P6_10") (class "Default")
      (node (ref "J10") (pin "P$31") (pinfunction "P$31_P$31") (pintype "bidirectional"))
    )
    (net (code "107") (name "P6_11") (class "Default")
      (node (ref "J10") (pin "P$30") (pinfunction "P$30_P$30") (pintype "bidirectional"))
    )
    (net (code "108") (name "P6_12") (class "Default")
      (node (ref "J10") (pin "P$29") (pinfunction "P$29_P$29") (pintype "bidirectional"))
    )
    (net (code "109") (name "P6_13") (class "Default")
      (node (ref "J10") (pin "P$28") (pinfunction "P$28_P$28") (pintype "bidirectional"))
    )
    (net (code "110") (name "P6_14") (class "Default")
      (node (ref "J10") (pin "P$27") (pinfunction "P$27_P$27") (pintype "bidirectional"))
    )
    (net (code "111") (name "P6_15") (class "Default")
      (node (ref "J10") (pin "P$26") (pinfunction "P$26_P$26") (pintype "bidirectional"))
    )
    (net (code "112") (name "P7") (class "Default")
      (node (ref "J2") (pin "7") (pinfunction "7_7") (pintype "passive"))
      (node (ref "RYS2") (pin "P$1") (pinfunction "1_P$1") (pintype "passive"))
    )
    (net (code "113") (name "P8") (class "Default")
      (node (ref "J2") (pin "8") (pinfunction "8_8") (pintype "passive"))
      (node (ref "RYS9") (pin "P$1") (pinfunction "1_P$1") (pintype "passive"))
    )
    (net (code "114") (name "P8_00") (class "Default")
      (node (ref "J10") (pin "P$4") (pinfunction "P$4_P$4") (pintype "bidirectional"))
    )
    (net (code "115") (name "P8_01") (class "Default")
      (node (ref "J10") (pin "P$3") (pinfunction "P$3_P$3") (pintype "bidirectional"))
    )
    (net (code "116") (name "P8_02") (class "Default")
      (node (ref "J10") (pin "P$2") (pinfunction "P$2_P$2") (pintype "bidirectional"))
    )
    (net (code "117") (name "P9") (class "Default")
      (node (ref "J2") (pin "9") (pinfunction "9_9") (pintype "passive"))
      (node (ref "RYS1") (pin "P$1") (pinfunction "1_P$1") (pintype "passive"))
    )
    (net (code "118") (name "P10") (class "Default")
      (node (ref "J2") (pin "10") (pinfunction "10_10") (pintype "passive"))
      (node (ref "RYS6") (pin "P$1") (pinfunction "1_P$1") (pintype "passive"))
    )
    (net (code "119") (name "PA_00") (class "Default")
      (node (ref "J10") (pin "P$21") (pinfunction "P$21_P$21") (pintype "bidirectional"))
    )
    (net (code "120") (name "PA_01") (class "Default")
      (node (ref "J10") (pin "P$22") (pinfunction "P$22_P$22") (pintype "bidirectional"))
    )
    (net (code "121") (name "PA_08") (class "Default")
      (node (ref "J10") (pin "P$25") (pinfunction "P$25_P$25") (pintype "bidirectional"))
    )
    (net (code "122") (name "PA_09") (class "Default")
      (node (ref "J10") (pin "P$24") (pinfunction "P$24_P$24") (pintype "bidirectional"))
    )
    (net (code "123") (name "PA_10") (class "Default")
      (node (ref "J10") (pin "P$23") (pinfunction "P$23_P$23") (pintype "bidirectional"))
    )
    (net (code "124") (name "VDD") (class "Default")
      (node (ref "J1") (pin "3") (pinfunction "3_3") (pintype "passive"))
      (node (ref "J1") (pin "4") (pinfunction "4_4") (pintype "passive"))
      (node (ref "R1") (pin "P$1") (pinfunction "1_P$1") (pintype "passive"))
      (node (ref "R10") (pin "P$1") (pinfunction "1_P$1") (pintype "passive"))
      (node (ref "R11") (pin "P$1") (pinfunction "1_P$1") (pintype "passive"))
      (node (ref "R12") (pin "P$1") (pinfunction "1_P$1") (pintype "passive"))
      (node (ref "R13") (pin "P$2") (pinfunction "2_P$2") (pintype "passive"))
      (node (ref "R14") (pin "P$1") (pinfunction "1_P$1") (pintype "passive"))
      (node (ref "R15") (pin "P$1") (pinfunction "1_P$1") (pintype "passive"))
      (node (ref "R16") (pin "P$1") (pinfunction "1_P$1") (pintype "passive"))
      (node (ref "R17") (pin "P$1") (pinfunction "1_P$1") (pintype "passive"))
      (node (ref "R2") (pin "P$1") (pinfunction "1_P$1") (pintype "passive"))
      (node (ref "R23") (pin "P$2") (pinfunction "2_P$2") (pintype "passive"))
      (node (ref "R24") (pin "P$2") (pinfunction "2_P$2") (pintype "passive"))
      (node (ref "R25") (pin "P$2") (pinfunction "2_P$2") (pintype "passive"))
      (node (ref "R26") (pin "P$2") (pinfunction "2_P$2") (pintype "passive"))
      (node (ref "R27") (pin "P$2") (pinfunction "2_P$2") (pintype "passive"))
      (node (ref "R28") (pin "P$2") (pinfunction "2_P$2") (pintype "passive"))
      (node (ref "R29") (pin "P$2") (pinfunction "2_P$2") (pintype "passive"))
      (node (ref "R3") (pin "P$1") (pinfunction "1_P$1") (pintype "passive"))
      (node (ref "R30") (pin "P$2") (pinfunction "2_P$2") (pintype "passive"))
      (node (ref "R32") (pin "P$2") (pinfunction "2_P$2") (pintype "passive"))
      (node (ref "R34") (pin "P$2") (pinfunction "2_P$2") (pintype "passive"))
      (node (ref "R4") (pin "P$1") (pinfunction "1_P$1") (pintype "passive"))
      (node (ref "R5") (pin "P$1") (pinfunction "1_P$1") (pintype "passive"))
      (node (ref "R6") (pin "P$1") (pinfunction "1_P$1") (pintype "passive"))
      (node (ref "R7") (pin "P$1") (pinfunction "1_P$1") (pintype "passive"))
      (node (ref "R8") (pin "P$1") (pinfunction "1_P$1") (pintype "passive"))
      (node (ref "R9") (pin "P$1") (pinfunction "1_P$1") (pintype "passive"))
    )
    (net (code "125") (name "VDD5") (class "Default")
      (node (ref "J1") (pin "5") (pinfunction "5_5") (pintype "passive"))
      (node (ref "J1") (pin "6") (pinfunction "6_6") (pintype "passive"))
    )
    (net (code "126") (name "VDD12") (class "Default")
      (node (ref "J1") (pin "7") (pinfunction "7_7") (pintype "passive"))
      (node (ref "J1") (pin "8") (pinfunction "8_8") (pintype "passive"))
    )
  )
)
